# ClockGenerator.net
KiCad netlist of a schematic drawn in EAGLE
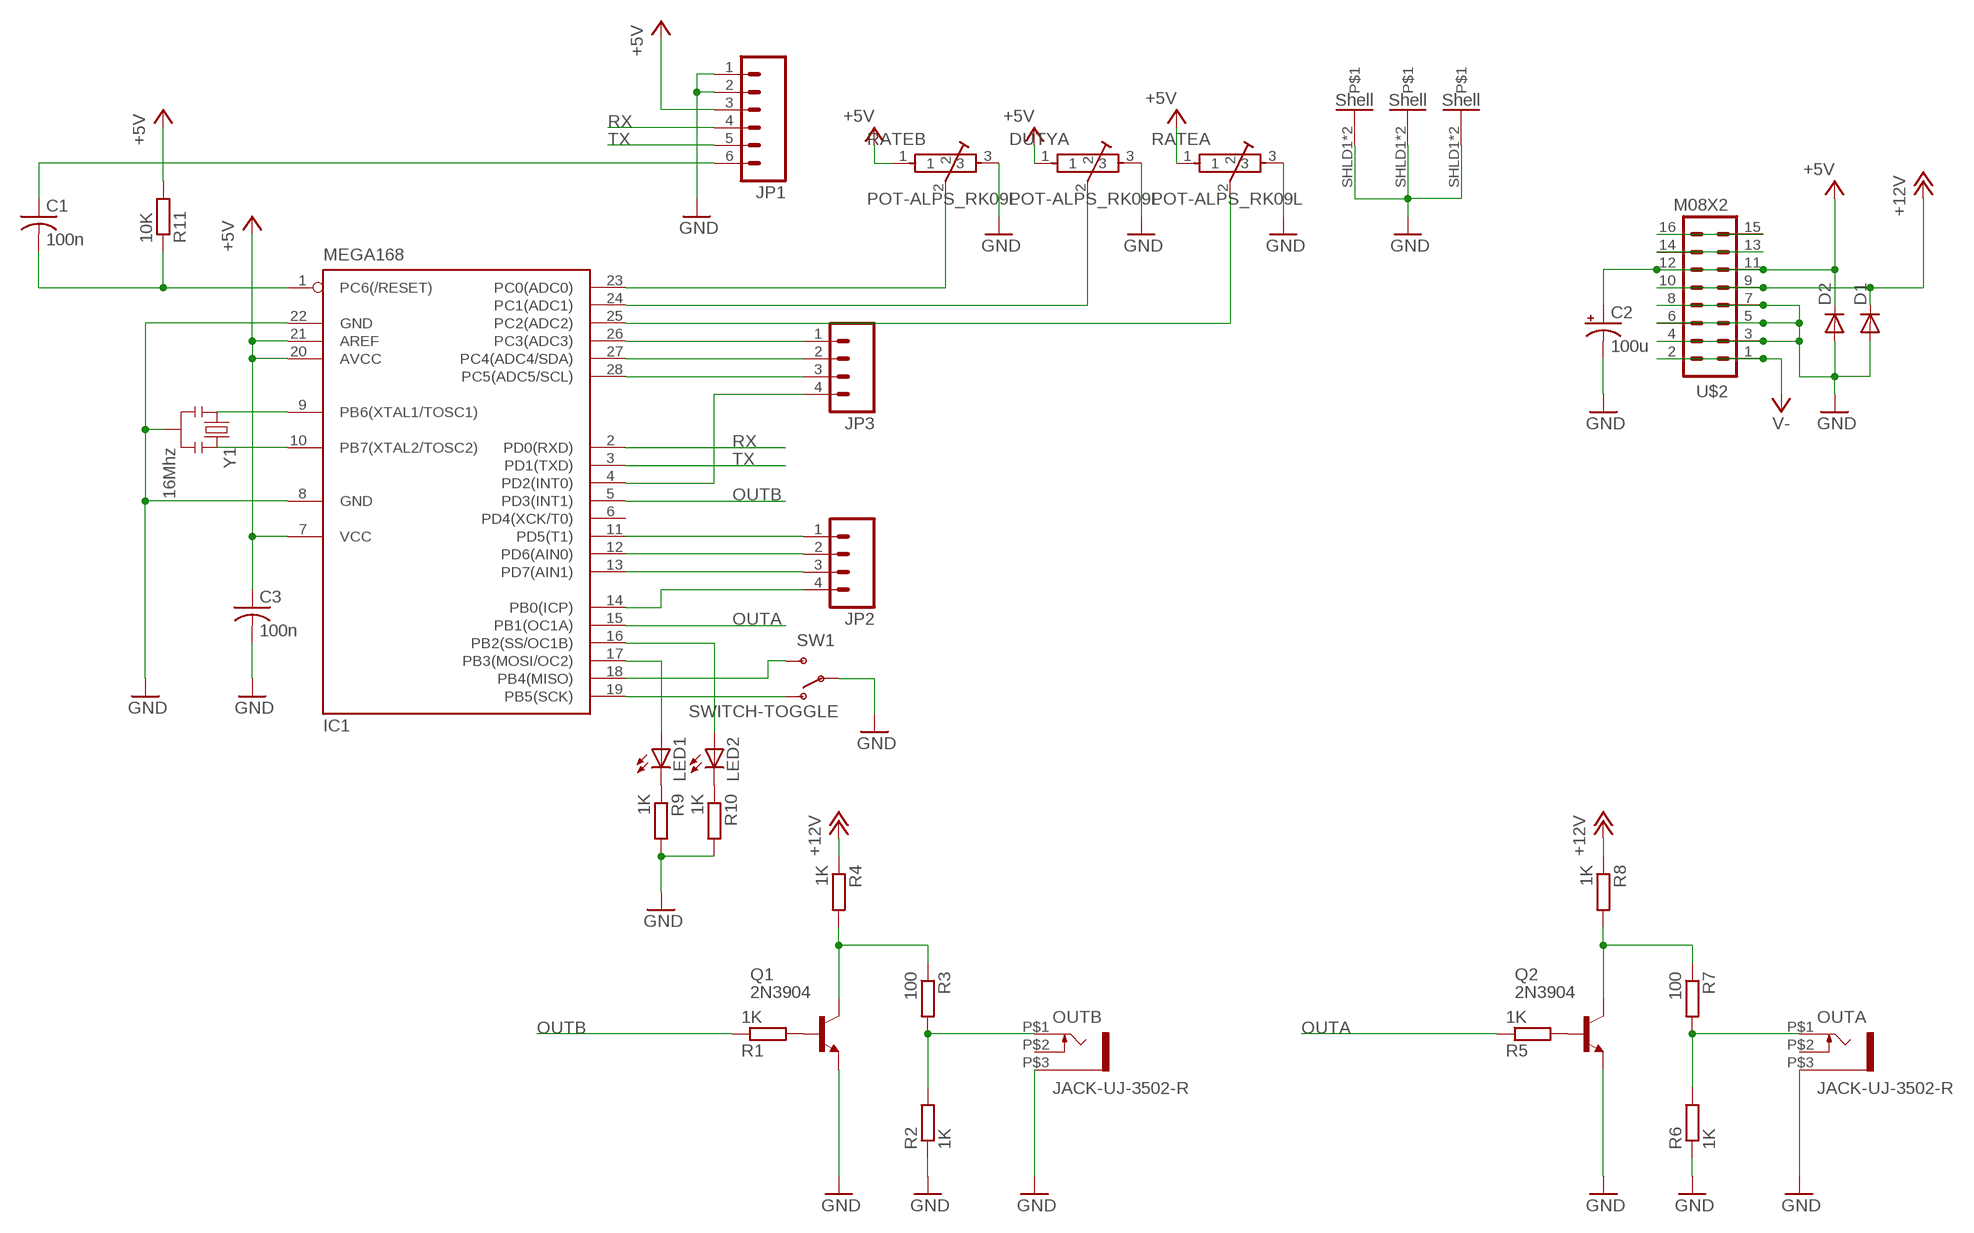
[diagram p0: schematic, sheet 1]

(export (version "E")
  (design (tool "Eeschema 10.0.6"))
  (components
    (comp (ref "C1")
      (value "100n")
      (footprint "eagle-import:C050-024X044")
      (libsource (lib "eagle-import") (part "C-US050-024X044"))
    )
    (comp (ref "C2")
      (value "100u")
      (footprint "eagle-import:CPOL-RADIAL-100UF-25V")
      (libsource (lib "eagle-import") (part "CAP_POLPTH1"))
    )
    (comp (ref "C3")
      (value "100n")
      (footprint "eagle-import:C050-024X044")
      (libsource (lib "eagle-import") (part "C-US050-024X044"))
    )
    (comp (ref "D1")
      (value "DIODEPTH")
      (footprint "eagle-import:DIODE-1N4001")
      (libsource (lib "eagle-import") (part "DIODEPTH"))
    )
    (comp (ref "D2")
      (value "DIODEPTH")
      (footprint "eagle-import:DIODE-1N4001")
      (libsource (lib "eagle-import") (part "DIODEPTH"))
    )
    (comp (ref "DUTYA")
      (value "POT-ALPS_RK09L")
      (footprint "eagle-import:POT-ALPS_RK09L1120")
      (libsource (lib "eagle-import") (part "POT-ALPS_RK09L"))
    )
    (comp (ref "IC1")
      (value "MEGA168")
      (footprint "eagle-import:DIL28-3")
      (libsource (lib "eagle-import") (part "MEGA8-P"))
    )
    (comp (ref "JP1")
      (value "M06SIP")
      (footprint "eagle-import:1X06")
      (libsource (lib "eagle-import") (part "M06SIP"))
    )
    (comp (ref "JP2")
      (value "M04PTH")
      (footprint "eagle-import:1X04")
      (libsource (lib "eagle-import") (part "M04PTH"))
    )
    (comp (ref "JP3")
      (value "M04PTH")
      (footprint "eagle-import:1X04")
      (libsource (lib "eagle-import") (part "M04PTH"))
    )
    (comp (ref "LED1")
      (value "LED3MM")
      (footprint "eagle-import:LED3MM")
      (libsource (lib "eagle-import") (part "LED3MM"))
    )
    (comp (ref "LED2")
      (value "LED3MM")
      (footprint "eagle-import:LED3MM")
      (libsource (lib "eagle-import") (part "LED3MM"))
    )
    (comp (ref "OUTA")
      (value "JACK-UJ-3502-R")
      (footprint "eagle-import:UJ-3502-R")
      (libsource (lib "eagle-import") (part "JACK-UJ-3502-R"))
    )
    (comp (ref "OUTB")
      (value "JACK-UJ-3502-R")
      (footprint "eagle-import:UJ-3502-R")
      (libsource (lib "eagle-import") (part "JACK-UJ-3502-R"))
    )
    (comp (ref "Q1")
      (value "2N3904")
      (footprint "eagle-import:TO92")
      (libsource (lib "eagle-import") (part "2N3904"))
    )
    (comp (ref "Q2")
      (value "2N3904")
      (footprint "eagle-import:TO92")
      (libsource (lib "eagle-import") (part "2N3904"))
    )
    (comp (ref "R1")
      (value "1K")
      (footprint "eagle-import:0204_7")
      (libsource (lib "eagle-import") (part "R-EU_0204/7"))
    )
    (comp (ref "R2")
      (value "1K")
      (footprint "eagle-import:0204_7")
      (libsource (lib "eagle-import") (part "R-EU_0204/7"))
    )
    (comp (ref "R3")
      (value "100")
      (footprint "eagle-import:0204_7")
      (libsource (lib "eagle-import") (part "R-EU_0204/7"))
    )
    (comp (ref "R4")
      (value "1K")
      (footprint "eagle-import:0204_7")
      (libsource (lib "eagle-import") (part "R-EU_0204/7"))
    )
    (comp (ref "R5")
      (value "1K")
      (footprint "eagle-import:0204_7")
      (libsource (lib "eagle-import") (part "R-EU_0204/7"))
    )
    (comp (ref "R6")
      (value "1K")
      (footprint "eagle-import:0204_7")
      (libsource (lib "eagle-import") (part "R-EU_0204/7"))
    )
    (comp (ref "R7")
      (value "100")
      (footprint "eagle-import:0204_7")
      (libsource (lib "eagle-import") (part "R-EU_0204/7"))
    )
    (comp (ref "R8")
      (value "1K")
      (footprint "eagle-import:0204_7")
      (libsource (lib "eagle-import") (part "R-EU_0204/7"))
    )
    (comp (ref "R9")
      (value "1K")
      (footprint "eagle-import:0204_7")
      (libsource (lib "eagle-import") (part "R-EU_0204/7"))
    )
    (comp (ref "R10")
      (value "1K")
      (footprint "eagle-import:0204_7")
      (libsource (lib "eagle-import") (part "R-EU_0204/7"))
    )
    (comp (ref "R11")
      (value "10K")
      (footprint "eagle-import:0204_7")
      (libsource (lib "eagle-import") (part "R-EU_0204/7"))
    )
    (comp (ref "RATEA")
      (value "POT-ALPS_RK09L")
      (footprint "eagle-import:POT-ALPS_RK09L1120")
      (libsource (lib "eagle-import") (part "POT-ALPS_RK09L"))
    )
    (comp (ref "RATEB")
      (value "POT-ALPS_RK09L")
      (footprint "eagle-import:POT-ALPS_RK09L1120")
      (libsource (lib "eagle-import") (part "POT-ALPS_RK09L"))
    )
    (comp (ref "SW1")
      (value "SWITCH-TOGGLE")
      (footprint "eagle-import:SWITCH-SPDT-SALECOM-T8020")
      (libsource (lib "eagle-import") (part "SWITCH-TOGGLE"))
    )
    (comp (ref "U$2")
      (value "M08X2")
      (footprint "eagle-import:2X8")
      (libsource (lib "eagle-import") (part "M08X2"))
    )
    (comp (ref "Y1")
      (value "16Mhz")
      (footprint "eagle-import:RESONATOR-PTH")
      (libsource (lib "eagle-import") (part "RESONATORPTH"))
    )
  )
  (nets
    (net (code "1") (name "+5V") (class "Default")
      (node (ref "C2") (pin "1") (pinfunction "+_1") (pintype "passive"))
      (node (ref "C3") (pin "1") (pinfunction "1_1") (pintype "passive"))
      (node (ref "D2") (pin "C") (pinfunction "C_C") (pintype "passive"))
      (node (ref "DUTYA") (pin "1") (pinfunction "1_1") (pintype "bidirectional"))
      (node (ref "IC1") (pin "20") (pinfunction "AVCC_20") (pintype "power_in"))
      (node (ref "IC1") (pin "21") (pinfunction "AREF_21") (pintype "passive"))
      (node (ref "IC1") (pin "7") (pinfunction "VCC_7") (pintype "power_in"))
      (node (ref "JP1") (pin "3") (pinfunction "3_3") (pintype "passive"))
      (node (ref "R11") (pin "2") (pinfunction "2_2") (pintype "passive"))
      (node (ref "RATEA") (pin "1") (pinfunction "1_1") (pintype "bidirectional"))
      (node (ref "RATEB") (pin "1") (pinfunction "1_1") (pintype "bidirectional"))
      (node (ref "U$2") (pin "11") (pinfunction "11_11") (pintype "passive"))
      (node (ref "U$2") (pin "12") (pinfunction "12_12") (pintype "passive"))
    )
    (net (code "2") (name "+12V") (class "Default")
      (node (ref "D1") (pin "C") (pinfunction "C_C") (pintype "passive"))
      (node (ref "R4") (pin "1") (pinfunction "1_1") (pintype "passive"))
      (node (ref "R8") (pin "1") (pinfunction "1_1") (pintype "passive"))
      (node (ref "U$2") (pin "10") (pinfunction "10_10") (pintype "passive"))
      (node (ref "U$2") (pin "9") (pinfunction "9_9") (pintype "passive"))
    )
    (net (code "3") (name "/OUTA") (class "Default")
      (node (ref "IC1") (pin "15") (pinfunction "PB1(OC1A)_15") (pintype "bidirectional"))
      (node (ref "R5") (pin "1") (pinfunction "1_1") (pintype "passive"))
    )
    (net (code "4") (name "/OUTB") (class "Default")
      (node (ref "IC1") (pin "5") (pinfunction "PD3(INT1)_5") (pintype "bidirectional"))
      (node (ref "R1") (pin "1") (pinfunction "1_1") (pintype "passive"))
    )
    (net (code "5") (name "/RX") (class "Default")
      (node (ref "IC1") (pin "2") (pinfunction "PD0(RXD)_2") (pintype "bidirectional"))
      (node (ref "JP1") (pin "4") (pinfunction "4_4") (pintype "passive"))
    )
    (net (code "6") (name "/TX") (class "Default")
      (node (ref "IC1") (pin "3") (pinfunction "PD1(TXD)_3") (pintype "bidirectional"))
      (node (ref "JP1") (pin "5") (pinfunction "5_5") (pintype "passive"))
    )
    (net (code "7") (name "GND") (class "Default")
      (node (ref "C2") (pin "2") (pinfunction "-_2") (pintype "passive"))
      (node (ref "C3") (pin "2") (pinfunction "2_2") (pintype "passive"))
      (node (ref "D1") (pin "A") (pinfunction "A_A") (pintype "passive"))
      (node (ref "D2") (pin "A") (pinfunction "A_A") (pintype "passive"))
      (node (ref "DUTYA") (pin "3") (pinfunction "3_3") (pintype "bidirectional"))
      (node (ref "DUTYA") (pin "SHLD1") (pinfunction "P$1_SHLD1") (pintype "bidirectional"))
      (node (ref "DUTYA") (pin "SHLD2") (pinfunction "P$1_SHLD2") (pintype "bidirectional"))
      (node (ref "IC1") (pin "22") (pinfunction "GND_22") (pintype "power_in"))
      (node (ref "IC1") (pin "8") (pinfunction "GND_8") (pintype "power_in"))
      (node (ref "JP1") (pin "1") (pinfunction "1_1") (pintype "passive"))
      (node (ref "JP1") (pin "2") (pinfunction "2_2") (pintype "passive"))
      (node (ref "OUTA") (pin "P$3") (pinfunction "SLEEVE_P$3") (pintype "passive"))
      (node (ref "OUTB") (pin "P$3") (pinfunction "SLEEVE_P$3") (pintype "passive"))
      (node (ref "Q1") (pin "3") (pinfunction "E_3") (pintype "passive"))
      (node (ref "Q2") (pin "3") (pinfunction "E_3") (pintype "passive"))
      (node (ref "R10") (pin "2") (pinfunction "2_2") (pintype "passive"))
      (node (ref "R2") (pin "1") (pinfunction "1_1") (pintype "passive"))
      (node (ref "R6") (pin "1") (pinfunction "1_1") (pintype "passive"))
      (node (ref "R9") (pin "2") (pinfunction "2_2") (pintype "passive"))
      (node (ref "RATEA") (pin "3") (pinfunction "3_3") (pintype "bidirectional"))
      (node (ref "RATEA") (pin "SHLD1") (pinfunction "P$1_SHLD1") (pintype "bidirectional"))
      (node (ref "RATEA") (pin "SHLD2") (pinfunction "P$1_SHLD2") (pintype "bidirectional"))
      (node (ref "RATEB") (pin "3") (pinfunction "3_3") (pintype "bidirectional"))
      (node (ref "RATEB") (pin "SHLD1") (pinfunction "P$1_SHLD1") (pintype "bidirectional"))
      (node (ref "RATEB") (pin "SHLD2") (pinfunction "P$1_SHLD2") (pintype "bidirectional"))
      (node (ref "SW1") (pin "2") (pinfunction "P_2") (pintype "passive"))
      (node (ref "U$2") (pin "3") (pinfunction "3_3") (pintype "passive"))
      (node (ref "U$2") (pin "4") (pinfunction "4_4") (pintype "passive"))
      (node (ref "U$2") (pin "5") (pinfunction "5_5") (pintype "passive"))
      (node (ref "U$2") (pin "6") (pinfunction "6_6") (pintype "passive"))
      (node (ref "U$2") (pin "7") (pinfunction "7_7") (pintype "passive"))
      (node (ref "U$2") (pin "8") (pinfunction "8_8") (pintype "passive"))
      (node (ref "Y1") (pin "2") (pinfunction "2_2") (pintype "passive"))
    )
    (net (code "8") (name "Net-(C1-Pad1)") (class "Default")
      (node (ref "C1") (pin "1") (pinfunction "1_1") (pintype "passive"))
      (node (ref "JP1") (pin "6") (pinfunction "6_6") (pintype "passive"))
    )
    (net (code "9") (name "Net-(IC1-PB0(ICP))") (class "Default")
      (node (ref "IC1") (pin "14") (pinfunction "PB0(ICP)_14") (pintype "bidirectional"))
      (node (ref "JP2") (pin "4") (pinfunction "4_4") (pintype "passive"))
    )
    (net (code "10") (name "Net-(IC1-PB2(SS{slash}OC1B))") (class "Default")
      (node (ref "IC1") (pin "16") (pinfunction "PB2(SS/OC1B)_16") (pintype "bidirectional"))
      (node (ref "LED2") (pin "A") (pinfunction "A_A") (pintype "passive"))
    )
    (net (code "11") (name "Net-(IC1-PB3(MOSI{slash}OC2))") (class "Default")
      (node (ref "IC1") (pin "17") (pinfunction "PB3(MOSI/OC2)_17") (pintype "bidirectional"))
      (node (ref "LED1") (pin "A") (pinfunction "A_A") (pintype "passive"))
    )
    (net (code "12") (name "Net-(IC1-PB4(MISO))") (class "Default")
      (node (ref "IC1") (pin "18") (pinfunction "PB4(MISO)_18") (pintype "bidirectional"))
      (node (ref "SW1") (pin "3") (pinfunction "S_3") (pintype "passive"))
    )
    (net (code "13") (name "Net-(IC1-PB5(SCK))") (class "Default")
      (node (ref "IC1") (pin "19") (pinfunction "PB5(SCK)_19") (pintype "bidirectional"))
      (node (ref "SW1") (pin "1") (pinfunction "O_1") (pintype "passive"))
    )
    (net (code "14") (name "Net-(IC1-PB6(XTAL1{slash}TOSC1))") (class "Default")
      (node (ref "IC1") (pin "9") (pinfunction "PB6(XTAL1/TOSC1)_9") (pintype "bidirectional"))
      (node (ref "Y1") (pin "1") (pinfunction "1_1") (pintype "passive"))
    )
    (net (code "15") (name "Net-(IC1-PB7(XTAL2{slash}TOSC2))") (class "Default")
      (node (ref "IC1") (pin "10") (pinfunction "PB7(XTAL2/TOSC2)_10") (pintype "bidirectional"))
      (node (ref "Y1") (pin "3") (pinfunction "3_3") (pintype "passive"))
    )
    (net (code "16") (name "Net-(IC1-PC0(ADC0))") (class "Default")
      (node (ref "IC1") (pin "23") (pinfunction "PC0(ADC0)_23") (pintype "bidirectional"))
      (node (ref "RATEB") (pin "2") (pinfunction "2_2") (pintype "bidirectional"))
    )
    (net (code "17") (name "Net-(IC1-PC1(ADC1))") (class "Default")
      (node (ref "DUTYA") (pin "2") (pinfunction "2_2") (pintype "bidirectional"))
      (node (ref "IC1") (pin "24") (pinfunction "PC1(ADC1)_24") (pintype "bidirectional"))
    )
    (net (code "18") (name "Net-(IC1-PC2(ADC2))") (class "Default")
      (node (ref "IC1") (pin "25") (pinfunction "PC2(ADC2)_25") (pintype "bidirectional"))
      (node (ref "RATEA") (pin "2") (pinfunction "2_2") (pintype "bidirectional"))
    )
    (net (code "19") (name "Net-(IC1-PC3(ADC3))") (class "Default")
      (node (ref "IC1") (pin "26") (pinfunction "PC3(ADC3)_26") (pintype "bidirectional"))
      (node (ref "JP3") (pin "1") (pinfunction "1_1") (pintype "passive"))
    )
    (net (code "20") (name "Net-(IC1-PC4(ADC4{slash}SDA))") (class "Default")
      (node (ref "IC1") (pin "27") (pinfunction "PC4(ADC4/SDA)_27") (pintype "bidirectional"))
      (node (ref "JP3") (pin "2") (pinfunction "2_2") (pintype "passive"))
    )
    (net (code "21") (name "Net-(IC1-PC5(ADC5{slash}SCL))") (class "Default")
      (node (ref "IC1") (pin "28") (pinfunction "PC5(ADC5/SCL)_28") (pintype "bidirectional"))
      (node (ref "JP3") (pin "3") (pinfunction "3_3") (pintype "passive"))
    )
    (net (code "22") (name "Net-(IC1-PC6({slash}RESET))") (class "Default")
      (node (ref "C1") (pin "2") (pinfunction "2_2") (pintype "passive"))
      (node (ref "IC1") (pin "1") (pinfunction "PC6(/RESET)_1") (pintype "bidirectional"))
      (node (ref "R11") (pin "1") (pinfunction "1_1") (pintype "passive"))
    )
    (net (code "23") (name "Net-(IC1-PD2(INT0))") (class "Default")
      (node (ref "IC1") (pin "4") (pinfunction "PD2(INT0)_4") (pintype "bidirectional"))
      (node (ref "JP3") (pin "4") (pinfunction "4_4") (pintype "passive"))
    )
    (net (code "24") (name "Net-(IC1-PD5(T1))") (class "Default")
      (node (ref "IC1") (pin "11") (pinfunction "PD5(T1)_11") (pintype "bidirectional"))
      (node (ref "JP2") (pin "1") (pinfunction "1_1") (pintype "passive"))
    )
    (net (code "25") (name "Net-(IC1-PD6(AIN0))") (class "Default")
      (node (ref "IC1") (pin "12") (pinfunction "PD6(AIN0)_12") (pintype "bidirectional"))
      (node (ref "JP2") (pin "2") (pinfunction "2_2") (pintype "passive"))
    )
    (net (code "26") (name "Net-(IC1-PD7(AIN1))") (class "Default")
      (node (ref "IC1") (pin "13") (pinfunction "PD7(AIN1)_13") (pintype "bidirectional"))
      (node (ref "JP2") (pin "3") (pinfunction "3_3") (pintype "passive"))
    )
    (net (code "27") (name "Net-(LED1-C)") (class "Default")
      (node (ref "LED1") (pin "K") (pinfunction "C_K") (pintype "passive"))
      (node (ref "R9") (pin "1") (pinfunction "1_1") (pintype "passive"))
    )
    (net (code "28") (name "Net-(LED2-C)") (class "Default")
      (node (ref "LED2") (pin "K") (pinfunction "C_K") (pintype "passive"))
      (node (ref "R10") (pin "1") (pinfunction "1_1") (pintype "passive"))
    )
    (net (code "29") (name "Net-(OUTA-TIP)") (class "Default")
      (node (ref "OUTA") (pin "P$1") (pinfunction "TIP_P$1") (pintype "passive"))
      (node (ref "R6") (pin "2") (pinfunction "2_2") (pintype "passive"))
      (node (ref "R7") (pin "2") (pinfunction "2_2") (pintype "passive"))
    )
    (net (code "30") (name "Net-(OUTB-TIP)") (class "Default")
      (node (ref "OUTB") (pin "P$1") (pinfunction "TIP_P$1") (pintype "passive"))
      (node (ref "R2") (pin "2") (pinfunction "2_2") (pintype "passive"))
      (node (ref "R3") (pin "2") (pinfunction "2_2") (pintype "passive"))
    )
    (net (code "31") (name "Net-(Q1-B)") (class "Default")
      (node (ref "Q1") (pin "2") (pinfunction "B_2") (pintype "passive"))
      (node (ref "R1") (pin "2") (pinfunction "2_2") (pintype "passive"))
    )
    (net (code "32") (name "Net-(Q1-C)") (class "Default")
      (node (ref "Q1") (pin "1") (pinfunction "C_1") (pintype "passive"))
      (node (ref "R3") (pin "1") (pinfunction "1_1") (pintype "passive"))
      (node (ref "R4") (pin "2") (pinfunction "2_2") (pintype "passive"))
    )
    (net (code "33") (name "Net-(Q2-B)") (class "Default")
      (node (ref "Q2") (pin "2") (pinfunction "B_2") (pintype "passive"))
      (node (ref "R5") (pin "2") (pinfunction "2_2") (pintype "passive"))
    )
    (net (code "34") (name "Net-(Q2-C)") (class "Default")
      (node (ref "Q2") (pin "1") (pinfunction "C_1") (pintype "passive"))
      (node (ref "R7") (pin "1") (pinfunction "1_1") (pintype "passive"))
      (node (ref "R8") (pin "2") (pinfunction "2_2") (pintype "passive"))
    )
    (net (code "35") (name "Net-(U$2-Pad13)") (class "Default")
      (node (ref "U$2") (pin "13") (pinfunction "13_13") (pintype "passive"))
      (node (ref "U$2") (pin "14") (pinfunction "14_14") (pintype "passive"))
    )
    (net (code "36") (name "Net-(U$2-Pad15)") (class "Default")
      (node (ref "U$2") (pin "15") (pinfunction "15_15") (pintype "passive"))
      (node (ref "U$2") (pin "16") (pinfunction "16_16") (pintype "passive"))
    )
    (net (code "37") (name "V-") (class "Default")
      (node (ref "U$2") (pin "1") (pinfunction "1_1") (pintype "passive"))
      (node (ref "U$2") (pin "2") (pinfunction "2_2") (pintype "passive"))
    )
    (net (code "38") (name "unconnected-(IC1-PD4(XCK{slash}T0)-Pad6)") (class "Default")
      (node (ref "IC1") (pin "6") (pinfunction "PD4(XCK/T0)_6") (pintype "bidirectional"))
    )
    (net (code "39") (name "unconnected-(OUTA-SW-PadP$2)") (class "Default")
      (node (ref "OUTA") (pin "P$2") (pinfunction "SW_P$2") (pintype "passive"))
    )
    (net (code "40") (name "unconnected-(OUTB-SW-PadP$2)") (class "Default")
      (node (ref "OUTB") (pin "P$2") (pinfunction "SW_P$2") (pintype "passive"))
    )
  )
)
